# DecentralizeLV_LPDRV.net
KiCad netlist of a schematic drawn in Altium Designer
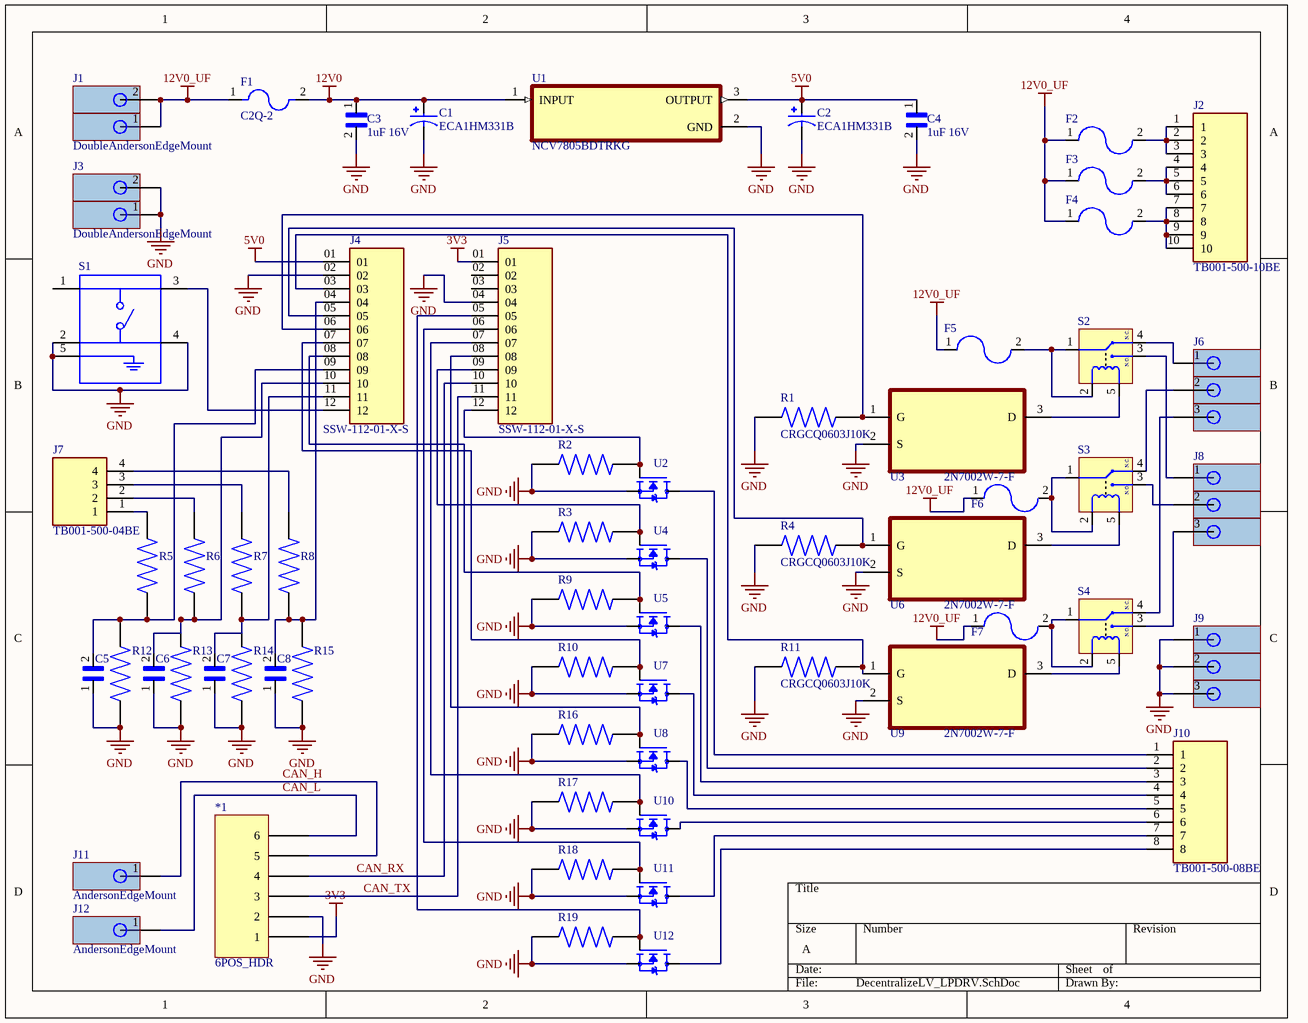
[diagram p0: DecentralizeLV_LPDRV.SchDoc]

(export (version "E")
  (design (tool "Eeschema 10.0.6"))
  (components
    (comp (ref "*1") (value "6POS_HDR") (footprint "6POS_HDR") (libsource (lib "MainLib") (part "6POS_HDR")))
    (comp (ref "C1")
      (value "ECA1HM331B")
      (footprint "CAPPRD500W60D1000H1600")
      (description "M-A")
      (fields (field (name "MF") "{'manufacturer': u'Panasonic Electronic'}"))
      (libsource (lib "SnapEDA_Library") (part "ECA1HM331B"))
    )
    (comp (ref "C2")
      (value "ECA1HM331B")
      (footprint "CAPPRD500W60D1000H1600")
      (description "M-A")
      (fields (field (name "MF") "{'manufacturer': u'Panasonic Electronic'}"))
      (libsource (lib "SnapEDA_Library") (part "ECA1HM331B"))
    )
    (comp (ref "C3")
      (value "1uF 16V")
      (footprint "CAPC2012X135N")
      (description "Cap Ceramic 1uF 16V X7R 10% Pad SMD 0805 125C T/R")
      (fields
        (field (name "MP") "CL21B105KOFNNNE")
        (field (name "MF") "{'manufacturer': u'Samsung Electro-Mechanics'}")
      )
      (libsource (lib "MCU_Lib") (part "CL21B105KOFNNNE"))
    )
    (comp (ref "C4")
      (value "1uF 16V")
      (footprint "CAPC2012X135N")
      (description "Cap Ceramic 1uF 16V X7R 10% Pad SMD 0805 125C T/R")
      (fields
        (field (name "MP") "CL21B105KOFNNNE")
        (field (name "MF") "{'manufacturer': u'Samsung Electro-Mechanics'}")
      )
      (libsource (lib "MCU_Lib") (part "CL21B105KOFNNNE"))
    )
    (comp (ref "C5")
      (value "CL10B104KA8NNNC")
      (footprint "CAPC1608X90N")
      (fields (field (name "MF") "{'manufacturer': u'Samsung Electro-Mechanics'}"))
      (libsource (lib "SnapEDA_Library") (part "CL10B104KA8NNNC"))
    )
    (comp (ref "C6")
      (value "CL10B104KA8NNNC")
      (footprint "CAPC1608X90N")
      (fields (field (name "MF") "{'manufacturer': u'Samsung Electro-Mechanics'}"))
      (libsource (lib "SnapEDA_Library") (part "CL10B104KA8NNNC"))
    )
    (comp (ref "C7")
      (value "CL10B104KA8NNNC")
      (footprint "CAPC1608X90N")
      (fields (field (name "MF") "{'manufacturer': u'Samsung Electro-Mechanics'}"))
      (libsource (lib "SnapEDA_Library") (part "CL10B104KA8NNNC"))
    )
    (comp (ref "C8")
      (value "CL10B104KA8NNNC")
      (footprint "CAPC1608X90N")
      (fields (field (name "MF") "{'manufacturer': u'Samsung Electro-Mechanics'}"))
      (libsource (lib "SnapEDA_Library") (part "CL10B104KA8NNNC"))
    )
    (comp (ref "F1")
      (value "C2Q-2")
      (footprint "FUSC1608X56N")
      (fields (field (name "MF") "{'manufacturer': u'Bel Fuse'}"))
      (libsource (lib "SnapEDA_Library") (part "C2Q-2"))
    )
    (comp (ref "F2")
      (value "MiniAutomotiveFuseHolder")
      (footprint "MiniBladeFuseHolder")
      (description "Blade Fuse Holder Automotive Mini")
      (libsource (lib "DecentralizeLV_LPDRV") (part "MiniBladeFuseHolder"))
    )
    (comp (ref "F3")
      (value "MiniAutomotiveFuseHolder")
      (footprint "MiniBladeFuseHolder")
      (description "Blade Fuse Holder Automotive Mini")
      (libsource (lib "DecentralizeLV_LPDRV") (part "MiniBladeFuseHolder"))
    )
    (comp (ref "F4")
      (value "MiniAutomotiveFuseHolder")
      (footprint "MiniBladeFuseHolder")
      (description "Blade Fuse Holder Automotive Mini")
      (libsource (lib "DecentralizeLV_LPDRV") (part "MiniBladeFuseHolder"))
    )
    (comp (ref "F5")
      (value "MiniAutomotiveFuseHolder")
      (footprint "MiniBladeFuseHolder")
      (description "Blade Fuse Holder Automotive Mini")
      (libsource (lib "DecentralizeLV_LPDRV") (part "MiniBladeFuseHolder"))
    )
    (comp (ref "F6")
      (value "MiniAutomotiveFuseHolder")
      (footprint "MiniBladeFuseHolder")
      (description "Blade Fuse Holder Automotive Mini")
      (libsource (lib "DecentralizeLV_LPDRV") (part "MiniBladeFuseHolder"))
    )
    (comp (ref "F7")
      (value "MiniAutomotiveFuseHolder")
      (footprint "MiniBladeFuseHolder")
      (description "Blade Fuse Holder Automotive Mini")
      (libsource (lib "DecentralizeLV_LPDRV") (part "MiniBladeFuseHolder"))
    )
    (comp (ref "J1")
      (value "DoubleAndersonEdgeMount")
      (footprint "DoubleAndersonEdgeMount")
      (description "Edge Mounted Anderson Connector")
      (libsource (lib "DecentralizeLV_LPDRV") (part "DoubleAndersonEdgeMount"))
    )
    (comp (ref "J2")
      (value "TB001-500-10BE")
      (footprint "CUI_TB001-500-10BE")
      (fields (field (name "MF") "{'manufacturer': u'CUI Devices'}"))
      (libsource (lib "SnapEDA_Library") (part "TB001-500-10BE"))
    )
    (comp (ref "J3")
      (value "DoubleAndersonEdgeMount")
      (footprint "DoubleAndersonEdgeMount")
      (description "Edge Mounted Anderson Connector")
      (libsource (lib "DecentralizeLV_LPDRV") (part "DoubleAndersonEdgeMount"))
    )
    (comp (ref "J4")
      (value "SSW-112-01-X-S")
      (footprint "SAMTEC_SSW-112-01-X-S")
      (description "CONN RCPT 12POS 0.1 GOLD PCB")
      (fields (field (name "MF") "{'manufacturer': u'Samtec'}"))
      (libsource (lib "SnapEDA_Library") (part "SSW-112-01-X-S"))
    )
    (comp (ref "J5")
      (value "SSW-112-01-X-S")
      (footprint "SAMTEC_SSW-112-01-X-S")
      (description "CONN RCPT 12POS 0.1 GOLD PCB")
      (fields (field (name "MF") "{'manufacturer': u'Samtec'}"))
      (libsource (lib "SnapEDA_Library") (part "SSW-112-01-X-S"))
    )
    (comp (ref "J6")
      (value "TripleAndersonEdgeMount")
      (footprint "TripleAndersonEdgeMount - duplicate")
      (description "Edge Mounted Anderson Connector")
      (libsource (lib "DecentralizeLV_LPDRV") (part "TripleAndersonEdgeMount"))
    )
    (comp (ref "J7")
      (value "TB001-500-04BE")
      (footprint "CUI_TB001-500-04BE")
      (fields (field (name "MF") "{'manufacturer': u'CUI Devices'}"))
      (libsource (lib "SnapEDA_Library") (part "TB001-500-04BE"))
    )
    (comp (ref "J8")
      (value "TripleAndersonEdgeMount")
      (footprint "TripleAndersonEdgeMount - duplicate")
      (description "Edge Mounted Anderson Connector")
      (libsource (lib "DecentralizeLV_LPDRV") (part "TripleAndersonEdgeMount"))
    )
    (comp (ref "J9")
      (value "TripleAndersonEdgeMount")
      (footprint "TripleAndersonEdgeMount - duplicate")
      (description "Edge Mounted Anderson Connector")
      (libsource (lib "DecentralizeLV_LPDRV") (part "TripleAndersonEdgeMount"))
    )
    (comp (ref "J10")
      (value "TB001-500-08BE")
      (footprint "CUI_TB001-500-08BE")
      (fields (field (name "MF") "{'manufacturer': u'CUI Devices'}"))
      (libsource (lib "SnapEDA_Library") (part "TB001-500-08BE"))
    )
    (comp (ref "J11")
      (value "AndersonEdgeMount")
      (footprint "AndersonEdgeMount")
      (description "Edge Mounted Anderson Connector")
      (libsource (lib "MainLib") (part "AndersonEdgeMount"))
    )
    (comp (ref "J12")
      (value "AndersonEdgeMount")
      (footprint "AndersonEdgeMount")
      (description "Edge Mounted Anderson Connector")
      (libsource (lib "MainLib") (part "AndersonEdgeMount"))
    )
    (comp (ref "R1")
      (value "CRGCQ0603J10K")
      (footprint "RESC1608X55N")
      (description "Fixed Resistor CRGCQ 0603 10K 5%")
      (fields (field (name "MF") "{'manufacturer': u'TE Connectivity'}"))
      (libsource (lib "MCU_Lib") (part "CRGCQ0603J10K"))
    )
    (comp (ref "R2")
      (value "CRGCQ0603J10K")
      (footprint "RESC1608X55N")
      (description "Fixed Resistor CRGCQ 0603 10K 5%")
      (fields (field (name "MF") "{'manufacturer': u'TE Connectivity'}"))
      (libsource (lib "MCU_Lib") (part "CRGCQ0603J10K"))
    )
    (comp (ref "R3")
      (value "CRGCQ0603J10K")
      (footprint "RESC1608X55N")
      (description "Fixed Resistor CRGCQ 0603 10K 5%")
      (fields (field (name "MF") "{'manufacturer': u'TE Connectivity'}"))
      (libsource (lib "MCU_Lib") (part "CRGCQ0603J10K"))
    )
    (comp (ref "R4")
      (value "CRGCQ0603J10K")
      (footprint "RESC1608X55N")
      (description "Fixed Resistor CRGCQ 0603 10K 5%")
      (fields (field (name "MF") "{'manufacturer': u'TE Connectivity'}"))
      (libsource (lib "MCU_Lib") (part "CRGCQ0603J10K"))
    )
    (comp (ref "R5")
      (value "CRGCQ0603J10K")
      (footprint "RESC1608X55N")
      (description "Fixed Resistor CRGCQ 0603 10K 5%")
      (fields (field (name "MF") "{'manufacturer': u'TE Connectivity'}"))
      (libsource (lib "MCU_Lib") (part "CRGCQ0603J10K"))
    )
    (comp (ref "R6")
      (value "CRGCQ0603J10K")
      (footprint "RESC1608X55N")
      (description "Fixed Resistor CRGCQ 0603 10K 5%")
      (fields (field (name "MF") "{'manufacturer': u'TE Connectivity'}"))
      (libsource (lib "MCU_Lib") (part "CRGCQ0603J10K"))
    )
    (comp (ref "R7")
      (value "CRGCQ0603J10K")
      (footprint "RESC1608X55N")
      (description "Fixed Resistor CRGCQ 0603 10K 5%")
      (fields (field (name "MF") "{'manufacturer': u'TE Connectivity'}"))
      (libsource (lib "MCU_Lib") (part "CRGCQ0603J10K"))
    )
    (comp (ref "R8")
      (value "CRGCQ0603J10K")
      (footprint "RESC1608X55N")
      (description "Fixed Resistor CRGCQ 0603 10K 5%")
      (fields (field (name "MF") "{'manufacturer': u'TE Connectivity'}"))
      (libsource (lib "MCU_Lib") (part "CRGCQ0603J10K"))
    )
    (comp (ref "R9")
      (value "CRGCQ0603J10K")
      (footprint "RESC1608X55N")
      (description "Fixed Resistor CRGCQ 0603 10K 5%")
      (fields (field (name "MF") "{'manufacturer': u'TE Connectivity'}"))
      (libsource (lib "MCU_Lib") (part "CRGCQ0603J10K"))
    )
    (comp (ref "R10")
      (value "CRGCQ0603J10K")
      (footprint "RESC1608X55N")
      (description "Fixed Resistor CRGCQ 0603 10K 5%")
      (fields (field (name "MF") "{'manufacturer': u'TE Connectivity'}"))
      (libsource (lib "MCU_Lib") (part "CRGCQ0603J10K"))
    )
    (comp (ref "R11")
      (value "CRGCQ0603J10K")
      (footprint "RESC1608X55N")
      (description "Fixed Resistor CRGCQ 0603 10K 5%")
      (fields (field (name "MF") "{'manufacturer': u'TE Connectivity'}"))
      (libsource (lib "MCU_Lib") (part "CRGCQ0603J10K"))
    )
    (comp (ref "R12")
      (value "RMCF0603JT2K00")
      (footprint "RESC1508X55N")
      (fields (field (name "MF") "{'manufacturer': u'Stackpole Electronics Inc'}"))
      (libsource (lib "SnapEDA_Library") (part "RMCF0603JT2K00"))
    )
    (comp (ref "R13")
      (value "RMCF0603JT2K00")
      (footprint "RESC1508X55N")
      (fields (field (name "MF") "{'manufacturer': u'Stackpole Electronics Inc'}"))
      (libsource (lib "SnapEDA_Library") (part "RMCF0603JT2K00"))
    )
    (comp (ref "R14")
      (value "RMCF0603JT2K00")
      (footprint "RESC1508X55N")
      (fields (field (name "MF") "{'manufacturer': u'Stackpole Electronics Inc'}"))
      (libsource (lib "SnapEDA_Library") (part "RMCF0603JT2K00"))
    )
    (comp (ref "R15")
      (value "RMCF0603JT2K00")
      (footprint "RESC1508X55N")
      (fields (field (name "MF") "{'manufacturer': u'Stackpole Electronics Inc'}"))
      (libsource (lib "SnapEDA_Library") (part "RMCF0603JT2K00"))
    )
    (comp (ref "R16")
      (value "CRGCQ0603J10K")
      (footprint "RESC1608X55N")
      (description "Fixed Resistor CRGCQ 0603 10K 5%")
      (fields (field (name "MF") "{'manufacturer': u'TE Connectivity'}"))
      (libsource (lib "MCU_Lib") (part "CRGCQ0603J10K"))
    )
    (comp (ref "R17")
      (value "CRGCQ0603J10K")
      (footprint "RESC1608X55N")
      (description "Fixed Resistor CRGCQ 0603 10K 5%")
      (fields (field (name "MF") "{'manufacturer': u'TE Connectivity'}"))
      (libsource (lib "MCU_Lib") (part "CRGCQ0603J10K"))
    )
    (comp (ref "R18")
      (value "CRGCQ0603J10K")
      (footprint "RESC1608X55N")
      (description "Fixed Resistor CRGCQ 0603 10K 5%")
      (fields (field (name "MF") "{'manufacturer': u'TE Connectivity'}"))
      (libsource (lib "MCU_Lib") (part "CRGCQ0603J10K"))
    )
    (comp (ref "R19")
      (value "CRGCQ0603J10K")
      (footprint "RESC1608X55N")
      (description "Fixed Resistor CRGCQ 0603 10K 5%")
      (fields (field (name "MF") "{'manufacturer': u'TE Connectivity'}"))
      (libsource (lib "MCU_Lib") (part "CRGCQ0603J10K"))
    )
    (comp (ref "S1")
      (value "TS06-667-43-BK-260-G-SMT-TR")
      (footprint "SW_TS06-667-43-BK-260-G-SMT-TR")
      (fields (field (name "MF") "{'manufacturer': u'CUI Devices'}"))
      (libsource (lib "SnapEDA_Library") (part "TS06-667-43-BK-260-G-SMT-TR"))
    )
    (comp (ref "S2")
      (value "SPDT 12V Relay 16A")
      (footprint "G5LE-1-E DC12")
      (libsource (lib "DecentralizeLV_LPDRV") (part "G5LE-1-E DC12"))
    )
    (comp (ref "S3")
      (value "SPDT 12V Relay 16A")
      (footprint "G5LE-1-E DC12")
      (libsource (lib "DecentralizeLV_LPDRV") (part "G5LE-1-E DC12"))
    )
    (comp (ref "S4")
      (value "SPDT 12V Relay 16A")
      (footprint "G5LE-1-E DC12")
      (libsource (lib "DecentralizeLV_LPDRV") (part "G5LE-1-E DC12"))
    )
    (comp (ref "U1")
      (value "NCV7805BDTRKG")
      (footprint "DPAK229P990X238-4N")
      (fields (field (name "MF") "{'manufacturer': u'ON Semiconductor'}"))
      (libsource (lib "SnapEDA_Library") (part "NCV7805BDTRKG"))
    )
    (comp (ref "U2")
      (value "MOSFET N-CH")
      (footprint "ZXMN6A09GTA")
      (libsource (lib "DecentralizeLV_LPDRV") (part "ZXMN6A09GTA"))
    )
    (comp (ref "U3")
      (value "2N7002W-7-F")
      (footprint "SOT65P210X110-3N")
      (description "N-CHANNEL ENHANCEMENT MODE FIELD EFFECT TRANSISTOR")
      (fields (field (name "MF") "{'manufacturer': u'Diodes Zetex'}"))
      (libsource (lib "MCU_Lib") (part "2N7002W-7-F"))
    )
    (comp (ref "U4")
      (value "MOSFET N-CH")
      (footprint "ZXMN6A09GTA")
      (libsource (lib "DecentralizeLV_LPDRV") (part "ZXMN6A09GTA"))
    )
    (comp (ref "U5")
      (value "MOSFET N-CH")
      (footprint "ZXMN6A09GTA")
      (libsource (lib "DecentralizeLV_LPDRV") (part "ZXMN6A09GTA"))
    )
    (comp (ref "U6")
      (value "2N7002W-7-F")
      (footprint "SOT65P210X110-3N")
      (description "N-CHANNEL ENHANCEMENT MODE FIELD EFFECT TRANSISTOR")
      (fields (field (name "MF") "{'manufacturer': u'Diodes Zetex'}"))
      (libsource (lib "MCU_Lib") (part "2N7002W-7-F"))
    )
    (comp (ref "U7")
      (value "MOSFET N-CH")
      (footprint "ZXMN6A09GTA")
      (libsource (lib "DecentralizeLV_LPDRV") (part "ZXMN6A09GTA"))
    )
    (comp (ref "U8")
      (value "MOSFET N-CH")
      (footprint "ZXMN6A09GTA")
      (libsource (lib "DecentralizeLV_LPDRV") (part "ZXMN6A09GTA"))
    )
    (comp (ref "U9")
      (value "2N7002W-7-F")
      (footprint "SOT65P210X110-3N")
      (description "N-CHANNEL ENHANCEMENT MODE FIELD EFFECT TRANSISTOR")
      (fields (field (name "MF") "{'manufacturer': u'Diodes Zetex'}"))
      (libsource (lib "MCU_Lib") (part "2N7002W-7-F"))
    )
    (comp (ref "U10")
      (value "MOSFET N-CH")
      (footprint "ZXMN6A09GTA")
      (libsource (lib "DecentralizeLV_LPDRV") (part "ZXMN6A09GTA"))
    )
    (comp (ref "U11")
      (value "MOSFET N-CH")
      (footprint "ZXMN6A09GTA")
      (libsource (lib "DecentralizeLV_LPDRV") (part "ZXMN6A09GTA"))
    )
    (comp (ref "U12")
      (value "MOSFET N-CH")
      (footprint "ZXMN6A09GTA")
      (libsource (lib "DecentralizeLV_LPDRV") (part "ZXMN6A09GTA"))
    )
  )
  (nets
    (net (code "1") (name "/CAN_H") (class "Default")
      (node (ref "*1") (pin "5") (pinfunction "5_5") (pintype "passive"))
      (node (ref "J11") (pin "1") (pinfunction "1_1") (pintype "passive"))
    )
    (net (code "2") (name "/CAN_L") (class "Default")
      (node (ref "*1") (pin "6") (pinfunction "6_6") (pintype "passive"))
      (node (ref "J12") (pin "1") (pinfunction "1_1") (pintype "passive"))
    )
    (net (code "3") (name "/CAN_RX") (class "Default")
      (node (ref "*1") (pin "4") (pinfunction "4_4") (pintype "passive"))
      (node (ref "J5") (pin "10") (pinfunction "10_10") (pintype "passive"))
    )
    (net (code "4") (name "/CAN_TX") (class "Default")
      (node (ref "*1") (pin "3") (pinfunction "3_3") (pintype "passive"))
      (node (ref "J5") (pin "11") (pinfunction "11_11") (pintype "passive"))
    )
    (net (code "5") (name "3V3") (class "Default")
      (node (ref "*1") (pin "1") (pinfunction "1_1") (pintype "passive"))
      (node (ref "J5") (pin "01") (pinfunction "01_01") (pintype "passive"))
    )
    (net (code "6") (name "5V0") (class "Default")
      (node (ref "C2") (pin "P") (pinfunction "P_P") (pintype "passive"))
      (node (ref "C4") (pin "1") (pinfunction "1_1") (pintype "passive"))
      (node (ref "J4") (pin "01") (pinfunction "01_01") (pintype "passive"))
      (node (ref "U1") (pin "3") (pinfunction "OUTPUT_3") (pintype "output"))
    )
    (net (code "7") (name "12V0") (class "Default")
      (node (ref "C1") (pin "P") (pinfunction "P_P") (pintype "passive"))
      (node (ref "C3") (pin "1") (pinfunction "1_1") (pintype "passive"))
      (node (ref "F1") (pin "2") (pinfunction "2_2") (pintype "passive"))
      (node (ref "U1") (pin "1") (pinfunction "INPUT_1") (pintype "input"))
    )
    (net (code "8") (name "12V0_UF") (class "Default")
      (node (ref "F1") (pin "1") (pinfunction "1_1") (pintype "passive"))
      (node (ref "F2") (pin "1") (pinfunction "1_1") (pintype "passive"))
      (node (ref "F3") (pin "1") (pinfunction "1_1") (pintype "passive"))
      (node (ref "F4") (pin "1") (pinfunction "1_1") (pintype "passive"))
      (node (ref "F5") (pin "1") (pinfunction "1_1") (pintype "passive"))
      (node (ref "F6") (pin "1") (pinfunction "1_1") (pintype "passive"))
      (node (ref "F7") (pin "1") (pinfunction "1_1") (pintype "passive"))
      (node (ref "J1") (pin "1") (pinfunction "1_1") (pintype "passive"))
      (node (ref "J1") (pin "2") (pinfunction "2_2") (pintype "passive"))
    )
    (net (code "9") (name "GND") (class "Default")
      (node (ref "*1") (pin "2") (pinfunction "2_2") (pintype "passive"))
      (node (ref "C1") (pin "N") (pinfunction "N_N") (pintype "passive"))
      (node (ref "C2") (pin "N") (pinfunction "N_N") (pintype "passive"))
      (node (ref "C3") (pin "2") (pinfunction "2_2") (pintype "passive"))
      (node (ref "C4") (pin "2") (pinfunction "2_2") (pintype "passive"))
      (node (ref "C5") (pin "1") (pinfunction "1_1") (pintype "passive"))
      (node (ref "C6") (pin "1") (pinfunction "1_1") (pintype "passive"))
      (node (ref "C7") (pin "1") (pinfunction "1_1") (pintype "passive"))
      (node (ref "C8") (pin "1") (pinfunction "1_1") (pintype "passive"))
      (node (ref "J3") (pin "1") (pinfunction "1_1") (pintype "passive"))
      (node (ref "J3") (pin "2") (pinfunction "2_2") (pintype "passive"))
      (node (ref "J4") (pin "02") (pinfunction "02_02") (pintype "passive"))
      (node (ref "J5") (pin "04") (pinfunction "04_04") (pintype "passive"))
      (node (ref "J9") (pin "1") (pinfunction "1_1") (pintype "passive"))
      (node (ref "J9") (pin "2") (pinfunction "2_2") (pintype "passive"))
      (node (ref "J9") (pin "3") (pinfunction "3_3") (pintype "passive"))
      (node (ref "R1") (pin "2") (pinfunction "2_2") (pintype "passive"))
      (node (ref "R10") (pin "2") (pinfunction "2_2") (pintype "passive"))
      (node (ref "R11") (pin "2") (pinfunction "2_2") (pintype "passive"))
      (node (ref "R12") (pin "1") (pinfunction "1_1") (pintype "passive"))
      (node (ref "R13") (pin "1") (pinfunction "1_1") (pintype "passive"))
      (node (ref "R14") (pin "1") (pinfunction "1_1") (pintype "passive"))
      (node (ref "R15") (pin "1") (pinfunction "1_1") (pintype "passive"))
      (node (ref "R16") (pin "2") (pinfunction "2_2") (pintype "passive"))
      (node (ref "R17") (pin "2") (pinfunction "2_2") (pintype "passive"))
      (node (ref "R18") (pin "2") (pinfunction "2_2") (pintype "passive"))
      (node (ref "R19") (pin "2") (pinfunction "2_2") (pintype "passive"))
      (node (ref "R2") (pin "2") (pinfunction "2_2") (pintype "passive"))
      (node (ref "R3") (pin "2") (pinfunction "2_2") (pintype "passive"))
      (node (ref "R4") (pin "2") (pinfunction "2_2") (pintype "passive"))
      (node (ref "R9") (pin "2") (pinfunction "2_2") (pintype "passive"))
      (node (ref "S1") (pin "2") (pinfunction "2_2") (pintype "passive"))
      (node (ref "S1") (pin "4") (pinfunction "4_4") (pintype "passive"))
      (node (ref "S1") (pin "5") (pinfunction "5_5") (pintype "passive"))
      (node (ref "U1") (pin "2") (pinfunction "GND_2") (pintype "power_in"))
      (node (ref "U10") (pin "3") (pinfunction "3_3") (pintype "passive"))
      (node (ref "U11") (pin "3") (pinfunction "3_3") (pintype "passive"))
      (node (ref "U12") (pin "3") (pinfunction "3_3") (pintype "passive"))
      (node (ref "U2") (pin "3") (pinfunction "3_3") (pintype "passive"))
      (node (ref "U3") (pin "2") (pinfunction "S_2") (pintype "passive"))
      (node (ref "U4") (pin "3") (pinfunction "3_3") (pintype "passive"))
      (node (ref "U5") (pin "3") (pinfunction "3_3") (pintype "passive"))
      (node (ref "U6") (pin "2") (pinfunction "S_2") (pintype "passive"))
      (node (ref "U7") (pin "3") (pinfunction "3_3") (pintype "passive"))
      (node (ref "U8") (pin "3") (pinfunction "3_3") (pintype "passive"))
      (node (ref "U9") (pin "2") (pinfunction "S_2") (pintype "passive"))
    )
    (net (code "10") (name "Net-(C5-Pad2)") (class "Default")
      (node (ref "C5") (pin "2") (pinfunction "2_2") (pintype "passive"))
      (node (ref "J4") (pin "09") (pinfunction "09_09") (pintype "passive"))
      (node (ref "R12") (pin "2") (pinfunction "2_2") (pintype "passive"))
      (node (ref "R5") (pin "2") (pinfunction "2_2") (pintype "passive"))
    )
    (net (code "11") (name "Net-(C6-Pad2)") (class "Default")
      (node (ref "C6") (pin "2") (pinfunction "2_2") (pintype "passive"))
      (node (ref "J4") (pin "10") (pinfunction "10_10") (pintype "passive"))
      (node (ref "R13") (pin "2") (pinfunction "2_2") (pintype "passive"))
      (node (ref "R6") (pin "2") (pinfunction "2_2") (pintype "passive"))
    )
    (net (code "12") (name "Net-(C7-Pad2)") (class "Default")
      (node (ref "C7") (pin "2") (pinfunction "2_2") (pintype "passive"))
      (node (ref "J4") (pin "11") (pinfunction "11_11") (pintype "passive"))
      (node (ref "R14") (pin "2") (pinfunction "2_2") (pintype "passive"))
      (node (ref "R7") (pin "2") (pinfunction "2_2") (pintype "passive"))
    )
    (net (code "13") (name "Net-(C8-Pad2)") (class "Default")
      (node (ref "C8") (pin "2") (pinfunction "2_2") (pintype "passive"))
      (node (ref "J4") (pin "04") (pinfunction "04_04") (pintype "passive"))
      (node (ref "R15") (pin "2") (pinfunction "2_2") (pintype "passive"))
      (node (ref "R8") (pin "2") (pinfunction "2_2") (pintype "passive"))
    )
    (net (code "14") (name "Net-(F2-Pad2)") (class "Default")
      (node (ref "F2") (pin "2") (pinfunction "2_2") (pintype "passive"))
      (node (ref "J2") (pin "1") (pinfunction "1_1") (pintype "passive"))
      (node (ref "J2") (pin "2") (pinfunction "2_2") (pintype "passive"))
      (node (ref "J2") (pin "3") (pinfunction "3_3") (pintype "passive"))
    )
    (net (code "15") (name "Net-(F3-Pad2)") (class "Default")
      (node (ref "F3") (pin "2") (pinfunction "2_2") (pintype "passive"))
      (node (ref "J2") (pin "4") (pinfunction "4_4") (pintype "passive"))
      (node (ref "J2") (pin "5") (pinfunction "5_5") (pintype "passive"))
      (node (ref "J2") (pin "6") (pinfunction "6_6") (pintype "passive"))
    )
    (net (code "16") (name "Net-(F4-Pad2)") (class "Default")
      (node (ref "F4") (pin "2") (pinfunction "2_2") (pintype "passive"))
      (node (ref "J2") (pin "10") (pinfunction "10_10") (pintype "passive"))
      (node (ref "J2") (pin "7") (pinfunction "7_7") (pintype "passive"))
      (node (ref "J2") (pin "8") (pinfunction "8_8") (pintype "passive"))
      (node (ref "J2") (pin "9") (pinfunction "9_9") (pintype "passive"))
    )
    (net (code "17") (name "Net-(F5-Pad2)") (class "Default")
      (node (ref "F5") (pin "2") (pinfunction "2_2") (pintype "passive"))
      (node (ref "S2") (pin "1") (pinfunction "1_1") (pintype "passive"))
      (node (ref "S2") (pin "2") (pinfunction "2_2") (pintype "passive"))
    )
    (net (code "18") (name "Net-(F6-Pad2)") (class "Default")
      (node (ref "F6") (pin "2") (pinfunction "2_2") (pintype "passive"))
      (node (ref "S3") (pin "1") (pinfunction "1_1") (pintype "passive"))
      (node (ref "S3") (pin "2") (pinfunction "2_2") (pintype "passive"))
    )
    (net (code "19") (name "Net-(F7-Pad2)") (class "Default")
      (node (ref "F7") (pin "2") (pinfunction "2_2") (pintype "passive"))
      (node (ref "S4") (pin "1") (pinfunction "1_1") (pintype "passive"))
      (node (ref "S4") (pin "2") (pinfunction "2_2") (pintype "passive"))
    )
    (net (code "20") (name "Net-(J4-Pad07)") (class "Default")
      (node (ref "J4") (pin "07") (pinfunction "07_07") (pintype "passive"))
      (node (ref "R10") (pin "1") (pinfunction "1_1") (pintype "passive"))
      (node (ref "U7") (pin "1") (pinfunction "1_1") (pintype "passive"))
    )
    (net (code "21") (name "Net-(J4-Pad08)") (class "Default")
      (node (ref "J4") (pin "08") (pinfunction "08_08") (pintype "passive"))
      (node (ref "R9") (pin "1") (pinfunction "1_1") (pintype "passive"))
      (node (ref "U5") (pin "1") (pinfunction "1_1") (pintype "passive"))
    )
    (net (code "22") (name "Net-(J4-Pad12)") (class "Default")
      (node (ref "J4") (pin "12") (pinfunction "12_12") (pintype "passive"))
      (node (ref "S1") (pin "3") (pinfunction "3_3") (pintype "passive"))
    )
    (net (code "23") (name "Net-(J5-Pad05)") (class "Default")
      (node (ref "J5") (pin "05") (pinfunction "05_05") (pintype "passive"))
      (node (ref "R19") (pin "1") (pinfunction "1_1") (pintype "passive"))
      (node (ref "U12") (pin "1") (pinfunction "1_1") (pintype "passive"))
    )
    (net (code "24") (name "Net-(J5-Pad06)") (class "Default")
      (node (ref "J5") (pin "06") (pinfunction "06_06") (pintype "passive"))
      (node (ref "R18") (pin "1") (pinfunction "1_1") (pintype "passive"))
      (node (ref "U11") (pin "1") (pinfunction "1_1") (pintype "passive"))
    )
    (net (code "25") (name "Net-(J5-Pad07)") (class "Default")
      (node (ref "J5") (pin "07") (pinfunction "07_07") (pintype "passive"))
      (node (ref "R17") (pin "1") (pinfunction "1_1") (pintype "passive"))
      (node (ref "U10") (pin "1") (pinfunction "1_1") (pintype "passive"))
    )
    (net (code "26") (name "Net-(J5-Pad08)") (class "Default")
      (node (ref "J5") (pin "08") (pinfunction "08_08") (pintype "passive"))
      (node (ref "R16") (pin "1") (pinfunction "1_1") (pintype "passive"))
      (node (ref "U8") (pin "1") (pinfunction "1_1") (pintype "passive"))
    )
    (net (code "27") (name "Net-(J5-Pad09)") (class "Default")
      (node (ref "J5") (pin "09") (pinfunction "09_09") (pintype "passive"))
      (node (ref "R3") (pin "1") (pinfunction "1_1") (pintype "passive"))
      (node (ref "U4") (pin "1") (pinfunction "1_1") (pintype "passive"))
    )
    (net (code "28") (name "Net-(J5-Pad12)") (class "Default")
      (node (ref "J5") (pin "12") (pinfunction "12_12") (pintype "passive"))
      (node (ref "R2") (pin "1") (pinfunction "1_1") (pintype "passive"))
      (node (ref "U2") (pin "1") (pinfunction "1_1") (pintype "passive"))
    )
    (net (code "29") (name "Net-(J6-Pad1)") (class "Default")
      (node (ref "J6") (pin "1") (pinfunction "1_1") (pintype "passive"))
      (node (ref "S2") (pin "4") (pinfunction "4_4") (pintype "passive"))
    )
    (net (code "30") (name "Net-(J6-Pad2)") (class "Default")
      (node (ref "J6") (pin "2") (pinfunction "2_2") (pintype "passive"))
      (node (ref "S3") (pin "4") (pinfunction "4_4") (pintype "passive"))
    )
    (net (code "31") (name "Net-(J6-Pad3)") (class "Default")
      (node (ref "J6") (pin "3") (pinfunction "3_3") (pintype "passive"))
      (node (ref "S4") (pin "4") (pinfunction "4_4") (pintype "passive"))
    )
    (net (code "32") (name "Net-(J7-Pad1)") (class "Default")
      (node (ref "J7") (pin "1") (pinfunction "1_1") (pintype "passive"))
      (node (ref "R5") (pin "1") (pinfunction "1_1") (pintype "passive"))
    )
    (net (code "33") (name "Net-(J7-Pad2)") (class "Default")
      (node (ref "J7") (pin "2") (pinfunction "2_2") (pintype "passive"))
      (node (ref "R6") (pin "1") (pinfunction "1_1") (pintype "passive"))
    )
    (net (code "34") (name "Net-(J7-Pad3)") (class "Default")
      (node (ref "J7") (pin "3") (pinfunction "3_3") (pintype "passive"))
      (node (ref "R7") (pin "1") (pinfunction "1_1") (pintype "passive"))
    )
    (net (code "35") (name "Net-(J7-Pad4)") (class "Default")
      (node (ref "J7") (pin "4") (pinfunction "4_4") (pintype "passive"))
      (node (ref "R8") (pin "1") (pinfunction "1_1") (pintype "passive"))
    )
    (net (code "36") (name "Net-(J8-Pad1)") (class "Default")
      (node (ref "J8") (pin "1") (pinfunction "1_1") (pintype "passive"))
      (node (ref "S2") (pin "3") (pinfunction "3_3") (pintype "passive"))
    )
    (net (code "37") (name "Net-(J8-Pad2)") (class "Default")
      (node (ref "J8") (pin "2") (pinfunction "2_2") (pintype "passive"))
      (node (ref "S3") (pin "3") (pinfunction "3_3") (pintype "passive"))
    )
    (net (code "38") (name "Net-(J8-Pad3)") (class "Default")
      (node (ref "J8") (pin "3") (pinfunction "3_3") (pintype "passive"))
      (node (ref "S4") (pin "3") (pinfunction "3_3") (pintype "passive"))
    )
    (net (code "39") (name "Net-(J10-Pad1)") (class "Default")
      (node (ref "J10") (pin "1") (pinfunction "1_1") (pintype "passive"))
      (node (ref "U2") (pin "2") (pinfunction "2_2") (pintype "passive"))
    )
    (net (code "40") (name "Net-(J10-Pad2)") (class "Default")
      (node (ref "J10") (pin "2") (pinfunction "2_2") (pintype "passive"))
      (node (ref "U4") (pin "2") (pinfunction "2_2") (pintype "passive"))
    )
    (net (code "41") (name "Net-(J10-Pad3)") (class "Default")
      (node (ref "J10") (pin "3") (pinfunction "3_3") (pintype "passive"))
      (node (ref "U5") (pin "2") (pinfunction "2_2") (pintype "passive"))
    )
    (net (code "42") (name "Net-(J10-Pad4)") (class "Default")
      (node (ref "J10") (pin "4") (pinfunction "4_4") (pintype "passive"))
      (node (ref "U7") (pin "2") (pinfunction "2_2") (pintype "passive"))
    )
    (net (code "43") (name "Net-(J10-Pad5)") (class "Default")
      (node (ref "J10") (pin "5") (pinfunction "5_5") (pintype "passive"))
      (node (ref "U8") (pin "2") (pinfunction "2_2") (pintype "passive"))
    )
    (net (code "44") (name "Net-(J10-Pad6)") (class "Default")
      (node (ref "J10") (pin "6") (pinfunction "6_6") (pintype "passive"))
      (node (ref "U10") (pin "2") (pinfunction "2_2") (pintype "passive"))
    )
    (net (code "45") (name "Net-(J10-Pad7)") (class "Default")
      (node (ref "J10") (pin "7") (pinfunction "7_7") (pintype "passive"))
      (node (ref "U11") (pin "2") (pinfunction "2_2") (pintype "passive"))
    )
    (net (code "46") (name "Net-(J10-Pad8)") (class "Default")
      (node (ref "J10") (pin "8") (pinfunction "8_8") (pintype "passive"))
      (node (ref "U12") (pin "2") (pinfunction "2_2") (pintype "passive"))
    )
    (net (code "47") (name "Net-(U3-D)") (class "Default")
      (node (ref "S2") (pin "5") (pinfunction "5_5") (pintype "passive"))
      (node (ref "U3") (pin "3") (pinfunction "D_3") (pintype "passive"))
    )
    (net (code "48") (name "Net-(U3-G)") (class "Default")
      (node (ref "J4") (pin "06") (pinfunction "06_06") (pintype "passive"))
      (node (ref "R1") (pin "1") (pinfunction "1_1") (pintype "passive"))
      (node (ref "U3") (pin "1") (pinfunction "G_1") (pintype "passive"))
    )
    (net (code "49") (name "Net-(U6-D)") (class "Default")
      (node (ref "S3") (pin "5") (pinfunction "5_5") (pintype "passive"))
      (node (ref "U6") (pin "3") (pinfunction "D_3") (pintype "passive"))
    )
    (net (code "50") (name "Net-(U6-G)") (class "Default")
      (node (ref "J4") (pin "05") (pinfunction "05_05") (pintype "passive"))
      (node (ref "R4") (pin "1") (pinfunction "1_1") (pintype "passive"))
      (node (ref "U6") (pin "1") (pinfunction "G_1") (pintype "passive"))
    )
    (net (code "51") (name "Net-(U9-D)") (class "Default")
      (node (ref "S4") (pin "5") (pinfunction "5_5") (pintype "passive"))
      (node (ref "U9") (pin "3") (pinfunction "D_3") (pintype "passive"))
    )
    (net (code "52") (name "Net-(U9-G)") (class "Default")
      (node (ref "J4") (pin "03") (pinfunction "03_03") (pintype "passive"))
      (node (ref "R11") (pin "1") (pinfunction "1_1") (pintype "passive"))
      (node (ref "U9") (pin "1") (pinfunction "G_1") (pintype "passive"))
    )
    (net (code "53") (name "unconnected-(J5-Pad02)") (class "Default")
      (node (ref "J5") (pin "02") (pinfunction "02_02") (pintype "passive"))
    )
    (net (code "54") (name "unconnected-(J5-Pad03)") (class "Default")
      (node (ref "J5") (pin "03") (pinfunction "03_03") (pintype "passive"))
    )
    (net (code "55") (name "unconnected-(S1-Pad1)") (class "Default")
      (node (ref "S1") (pin "1") (pinfunction "1_1") (pintype "passive"))
    )
  )
)
